# SCH_Project-30-easy-XIAO_2026-04-27.net
KiCad netlist of a schematic drawn in EasyEDA
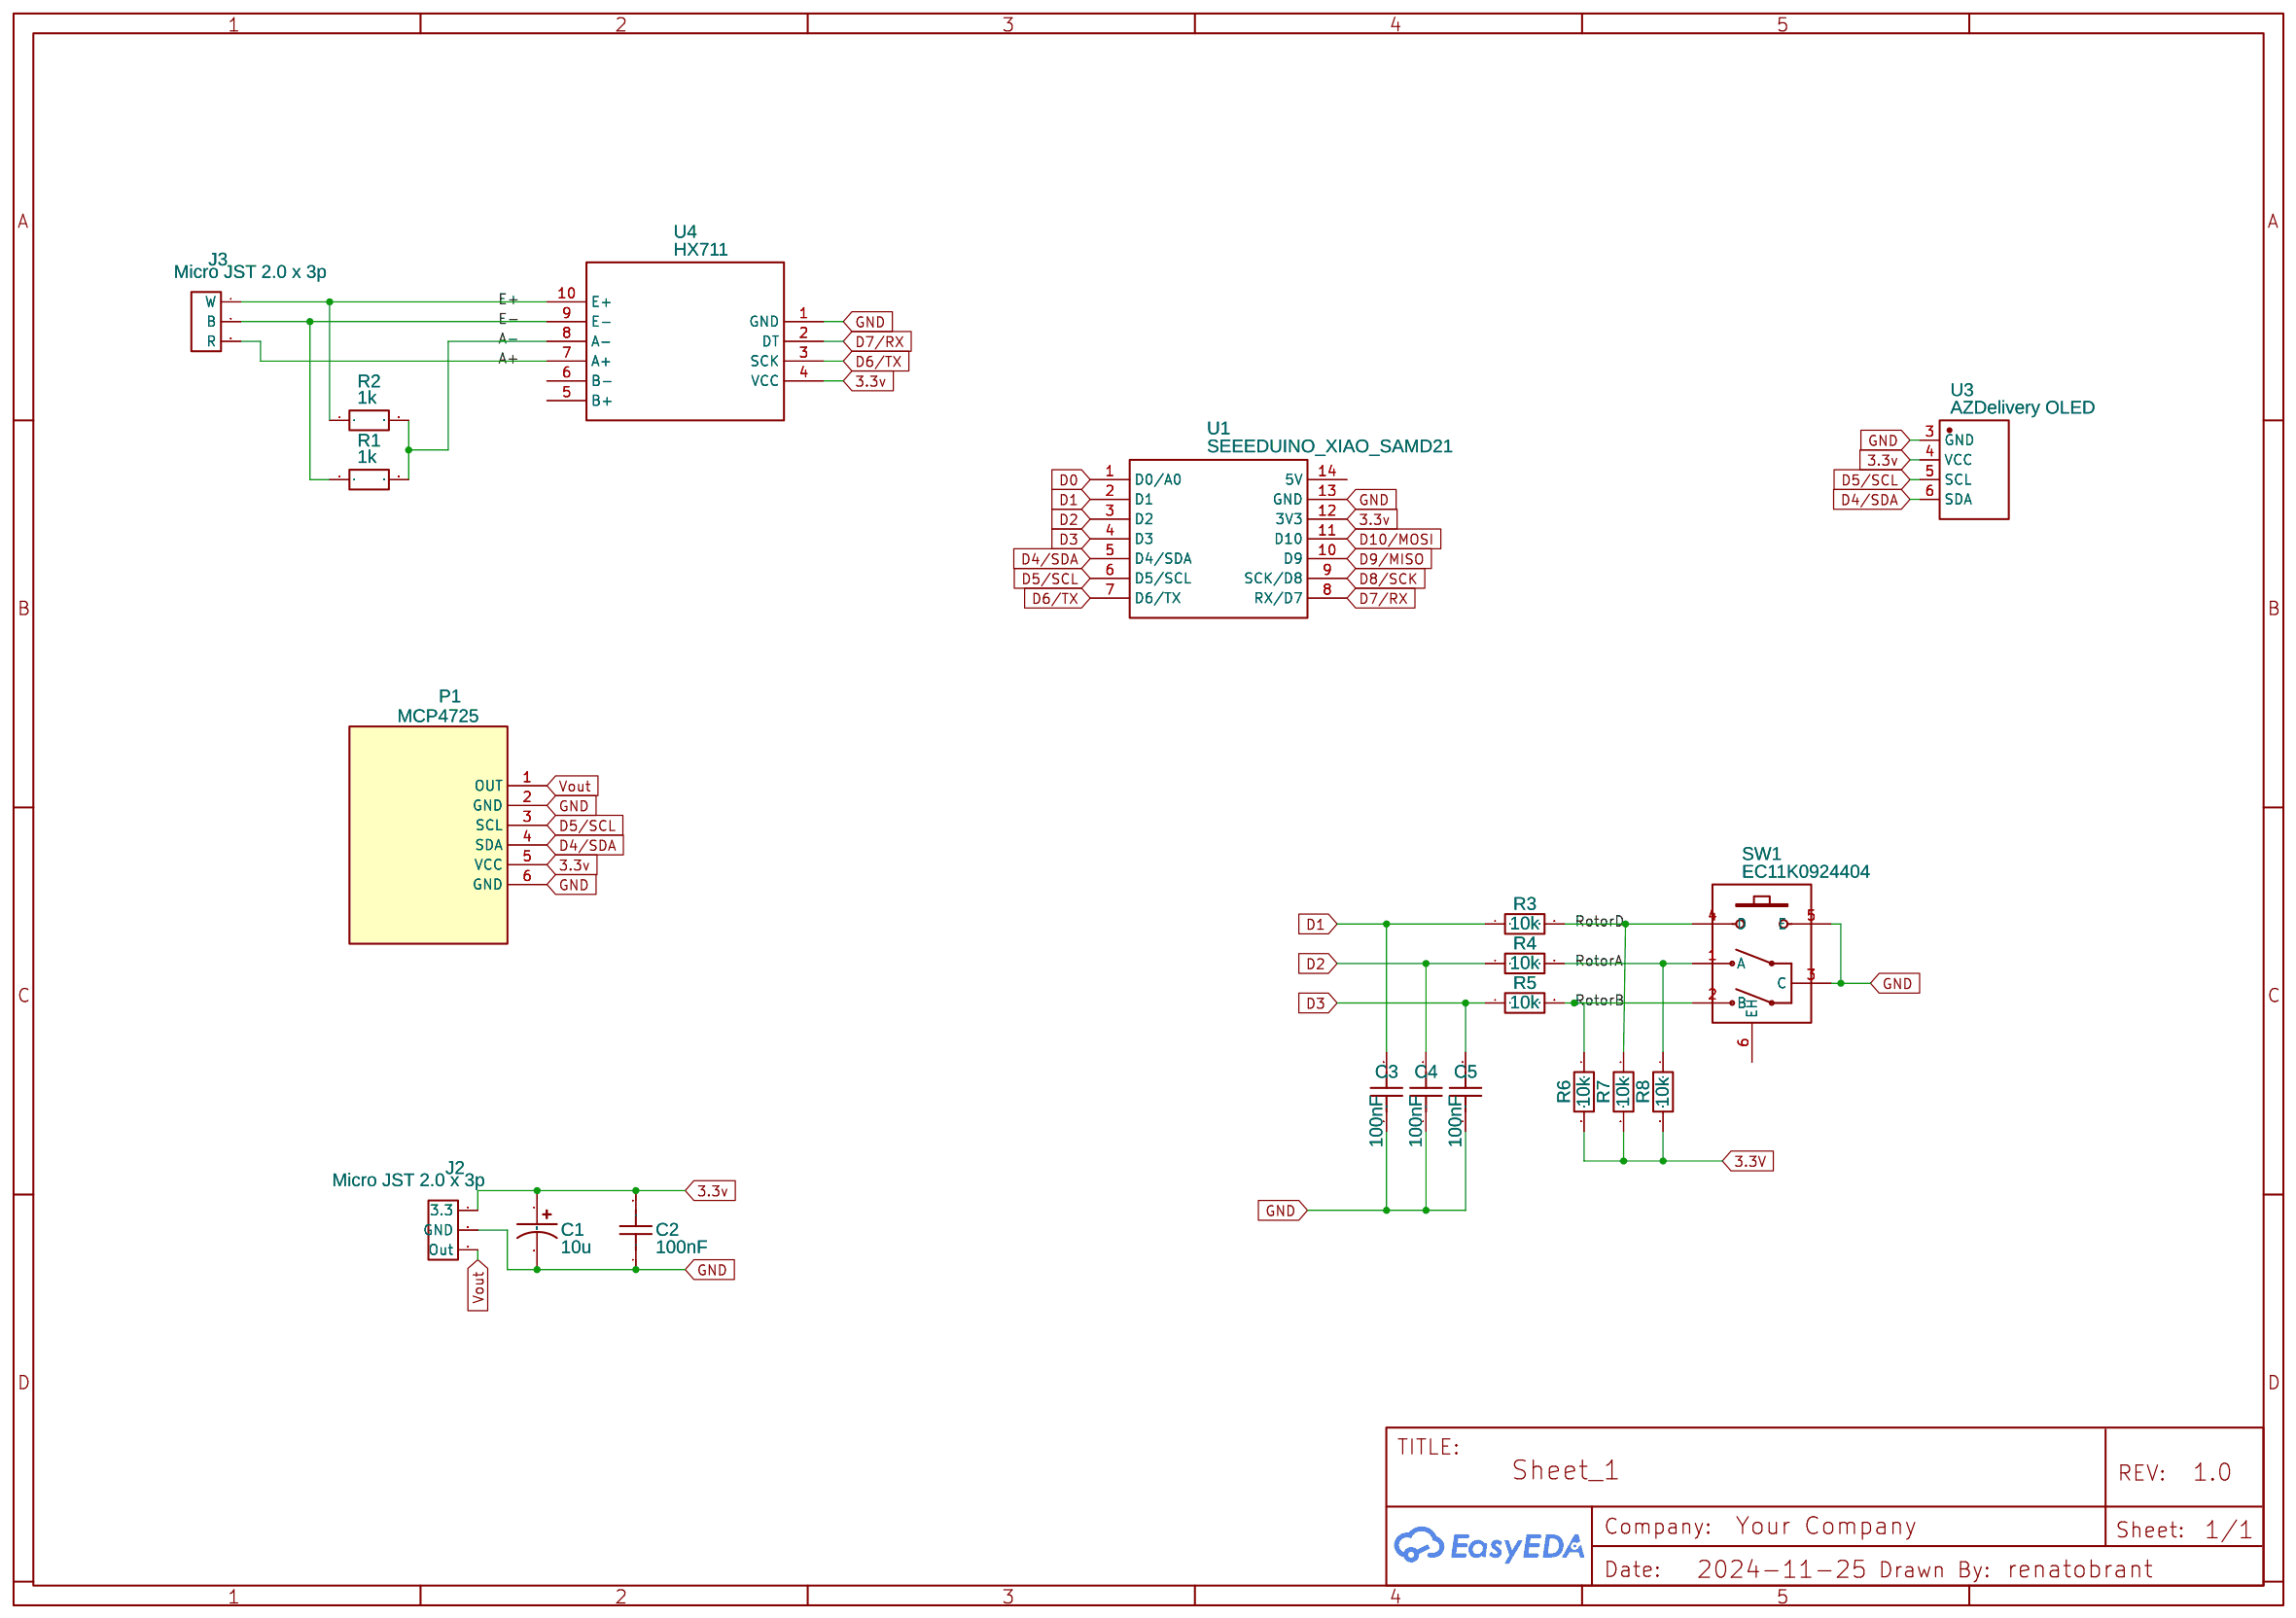
[diagram p0: schematic sheet]

(export (version "E")
  (design (tool "Eeschema 10.0.6"))
  (components
    (comp (ref "C1") (value "10u") (libsource (lib "") (part "CE_TH_D5.0×F2.0_US")))
    (comp (ref "C2") (value "100nF") (libsource (lib "") (part "C_RAD-0.1_US")))
    (comp (ref "C3") (value "100nF") (libsource (lib "") (part "C_RAD-0.1_US")))
    (comp (ref "C4") (value "100nF") (libsource (lib "") (part "C_RAD-0.1_US")))
    (comp (ref "C5") (value "100nF") (libsource (lib "") (part "C_RAD-0.1_US")))
    (comp (ref "J2") (value "Micro JST 2.0 x 3p") (libsource (lib "") (part "Micro JST 2.0 x 3p_1")))
    (comp (ref "J3") (value "Micro JST 2.0 x 3p") (libsource (lib "") (part "Micro JST 2.0 x 3p")))
    (comp (ref "P1") (value "MCP4725") (libsource (lib "") (part "MCP4725 COPY")))
    (comp (ref "R1") (value "1k") (libsource (lib "") (part "R_AXIAL-0.3_EU_1")))
    (comp (ref "R2") (value "1k") (libsource (lib "") (part "R_AXIAL-0.3_EU_1")))
    (comp (ref "R3") (value "10k") (libsource (lib "") (part "R_AXIAL-0.3_EU_1")))
    (comp (ref "R4") (value "10k") (libsource (lib "") (part "R_AXIAL-0.3_EU_1")))
    (comp (ref "R5") (value "10k") (libsource (lib "") (part "R_AXIAL-0.3_EU_1")))
    (comp (ref "R6") (value "10k") (libsource (lib "") (part "R_AXIAL-0.3_EU")))
    (comp (ref "R7") (value "10k") (libsource (lib "") (part "R_AXIAL-0.3_EU")))
    (comp (ref "R8") (value "10k") (libsource (lib "") (part "R_AXIAL-0.3_EU")))
    (comp (ref "SW1")
      (value "EC11K0924404")
      (fields (field (name "Manufacturer") "ALPSALPINE(阿尔卑斯阿尔派)"))
      (libsource (lib "") (part "EC11K0924404"))
    )
    (comp (ref "U1") (value "SEEEDUINO_XIAO_SAMD21") (libsource (lib "") (part "SEEEDUINO_XIAO_SAMD21")))
    (comp (ref "U3")
      (value "AZDelivery OLED")
      (fields
        (field (name "Manufacturer Part") "ZJY096S0700BG01蓝色")
        (field (name "Manufacturer") "AZDelivery")
      )
      (libsource (lib "") (part "AZDelivery OLED"))
    )
    (comp (ref "U4") (value "HX711") (libsource (lib "") (part "HX711")))
  )
  (nets
    (net (code "1") (name "/A+") (class "Default")
      (node (ref "J3") (pin "3") (pinfunction "R_3") (pintype "unspecified"))
      (node (ref "U4") (pin "7") (pinfunction "A+_7") (pintype "unspecified"))
    )
    (net (code "2") (name "/A-") (class "Default")
      (node (ref "R1") (pin "2") (pinfunction "2_2") (pintype "unspecified"))
      (node (ref "R2") (pin "2") (pinfunction "2_2") (pintype "unspecified"))
      (node (ref "U4") (pin "8") (pinfunction "A-_8") (pintype "unspecified"))
    )
    (net (code "3") (name "/E+") (class "Default")
      (node (ref "J3") (pin "1") (pinfunction "W_1") (pintype "unspecified"))
      (node (ref "R2") (pin "1") (pinfunction "1_1") (pintype "unspecified"))
      (node (ref "U4") (pin "10") (pinfunction "E+_10") (pintype "unspecified"))
    )
    (net (code "4") (name "/E-") (class "Default")
      (node (ref "J3") (pin "2") (pinfunction "B_2") (pintype "unspecified"))
      (node (ref "R1") (pin "1") (pinfunction "1_1") (pintype "unspecified"))
      (node (ref "U4") (pin "9") (pinfunction "E-_9") (pintype "unspecified"))
    )
    (net (code "5") (name "/RotorA") (class "Default")
      (node (ref "R4") (pin "2") (pinfunction "2_2") (pintype "unspecified"))
      (node (ref "R8") (pin "1") (pinfunction "1_1") (pintype "unspecified"))
      (node (ref "SW1") (pin "1") (pinfunction "A_1") (pintype "unspecified"))
    )
    (net (code "6") (name "/RotorB") (class "Default")
      (node (ref "R5") (pin "2") (pinfunction "2_2") (pintype "unspecified"))
      (node (ref "R6") (pin "1") (pinfunction "1_1") (pintype "unspecified"))
      (node (ref "SW1") (pin "2") (pinfunction "B_2") (pintype "unspecified"))
    )
    (net (code "7") (name "/RotorD") (class "Default")
      (node (ref "R3") (pin "2") (pinfunction "2_2") (pintype "unspecified"))
      (node (ref "R7") (pin "1") (pinfunction "1_1") (pintype "unspecified"))
      (node (ref "SW1") (pin "4") (pinfunction "D_4") (pintype "unspecified"))
    )
    (net (code "8") (name "3.3V") (class "Default")
      (node (ref "R6") (pin "2") (pinfunction "2_2") (pintype "unspecified"))
      (node (ref "R7") (pin "2") (pinfunction "2_2") (pintype "unspecified"))
      (node (ref "R8") (pin "2") (pinfunction "2_2") (pintype "unspecified"))
    )
    (net (code "9") (name "3.3v") (class "Default")
      (node (ref "C1") (pin "1") (pinfunction "1_1") (pintype "unspecified"))
      (node (ref "C2") (pin "2") (pinfunction "2_2") (pintype "unspecified"))
      (node (ref "J2") (pin "1") (pinfunction "3.3_1") (pintype "unspecified"))
      (node (ref "P1") (pin "5") (pinfunction "VCC_5") (pintype "unspecified"))
      (node (ref "U1") (pin "12") (pinfunction "3V3_12") (pintype "unspecified"))
      (node (ref "U3") (pin "4") (pinfunction "VCC_4") (pintype "unspecified"))
      (node (ref "U4") (pin "4") (pinfunction "VCC_4") (pintype "unspecified"))
    )
    (net (code "10") (name "D0") (class "Default")
      (node (ref "U1") (pin "1") (pinfunction "D0/A0_1") (pintype "unspecified"))
    )
    (net (code "11") (name "D1") (class "Default")
      (node (ref "C3") (pin "2") (pinfunction "2_2") (pintype "unspecified"))
      (node (ref "R3") (pin "1") (pinfunction "1_1") (pintype "unspecified"))
      (node (ref "U1") (pin "2") (pinfunction "D1_2") (pintype "unspecified"))
    )
    (net (code "12") (name "D2") (class "Default")
      (node (ref "C4") (pin "2") (pinfunction "2_2") (pintype "unspecified"))
      (node (ref "R4") (pin "1") (pinfunction "1_1") (pintype "unspecified"))
      (node (ref "U1") (pin "3") (pinfunction "D2_3") (pintype "unspecified"))
    )
    (net (code "13") (name "D3") (class "Default")
      (node (ref "C5") (pin "2") (pinfunction "2_2") (pintype "unspecified"))
      (node (ref "R5") (pin "1") (pinfunction "1_1") (pintype "unspecified"))
      (node (ref "U1") (pin "4") (pinfunction "D3_4") (pintype "unspecified"))
    )
    (net (code "14") (name "D4{slash}SDA") (class "Default")
      (node (ref "P1") (pin "4") (pinfunction "SDA_4") (pintype "unspecified"))
      (node (ref "U1") (pin "5") (pinfunction "D4/SDA_5") (pintype "unspecified"))
      (node (ref "U3") (pin "6") (pinfunction "SDA_6") (pintype "unspecified"))
    )
    (net (code "15") (name "D5{slash}SCL") (class "Default")
      (node (ref "P1") (pin "3") (pinfunction "SCL_3") (pintype "unspecified"))
      (node (ref "U1") (pin "6") (pinfunction "D5/SCL_6") (pintype "unspecified"))
      (node (ref "U3") (pin "5") (pinfunction "SCL_5") (pintype "unspecified"))
    )
    (net (code "16") (name "D6{slash}TX") (class "Default")
      (node (ref "U1") (pin "7") (pinfunction "D6/TX_7") (pintype "unspecified"))
      (node (ref "U4") (pin "3") (pinfunction "SCK_3") (pintype "unspecified"))
    )
    (net (code "17") (name "D7{slash}RX") (class "Default")
      (node (ref "U1") (pin "8") (pinfunction "RX/D7_8") (pintype "unspecified"))
      (node (ref "U4") (pin "2") (pinfunction "DT_2") (pintype "unspecified"))
    )
    (net (code "18") (name "D8{slash}SCK") (class "Default")
      (node (ref "U1") (pin "9") (pinfunction "SCK/D8_9") (pintype "unspecified"))
    )
    (net (code "19") (name "D9{slash}MISO") (class "Default")
      (node (ref "U1") (pin "10") (pinfunction "D9_10") (pintype "unspecified"))
    )
    (net (code "20") (name "D10{slash}MOSI") (class "Default")
      (node (ref "U1") (pin "11") (pinfunction "D10_11") (pintype "unspecified"))
    )
    (net (code "21") (name "GND") (class "Default")
      (node (ref "C1") (pin "2") (pinfunction "2_2") (pintype "unspecified"))
      (node (ref "C2") (pin "1") (pinfunction "1_1") (pintype "unspecified"))
      (node (ref "C3") (pin "1") (pinfunction "1_1") (pintype "unspecified"))
      (node (ref "C4") (pin "1") (pinfunction "1_1") (pintype "unspecified"))
      (node (ref "C5") (pin "1") (pinfunction "1_1") (pintype "unspecified"))
      (node (ref "J2") (pin "2") (pinfunction "GND_2") (pintype "unspecified"))
      (node (ref "P1") (pin "2") (pinfunction "GND_2") (pintype "unspecified"))
      (node (ref "P1") (pin "6") (pinfunction "GND_6") (pintype "unspecified"))
      (node (ref "SW1") (pin "3") (pinfunction "C_3") (pintype "unspecified"))
      (node (ref "SW1") (pin "5") (pinfunction "E_5") (pintype "unspecified"))
      (node (ref "U1") (pin "13") (pinfunction "GND_13") (pintype "unspecified"))
      (node (ref "U3") (pin "3") (pinfunction "GND_3") (pintype "unspecified"))
      (node (ref "U4") (pin "1") (pinfunction "GND_1") (pintype "unspecified"))
    )
    (net (code "22") (name "Vout") (class "Default")
      (node (ref "J2") (pin "3") (pinfunction "Out_3") (pintype "unspecified"))
      (node (ref "P1") (pin "1") (pinfunction "OUT_1") (pintype "unspecified"))
    )
    (net (code "23") (name "unconnected-(SW1-EH-Pad6)") (class "Default")
      (node (ref "SW1") (pin "6") (pinfunction "EH_6") (pintype "unspecified"))
    )
    (net (code "24") (name "unconnected-(U1-5V-Pad14)") (class "Default")
      (node (ref "U1") (pin "14") (pinfunction "5V_14") (pintype "unspecified"))
    )
    (net (code "25") (name "unconnected-(U4-B+-Pad5)") (class "Default")
      (node (ref "U4") (pin "5") (pinfunction "B+_5") (pintype "unspecified"))
    )
    (net (code "26") (name "unconnected-(U4-B--Pad6)") (class "Default")
      (node (ref "U4") (pin "6") (pinfunction "B-_6") (pintype "unspecified"))
    )
  )
)
